# eii-psu-thr-hole-psb.net
KiCad netlist of a schematic drawn in EAGLE
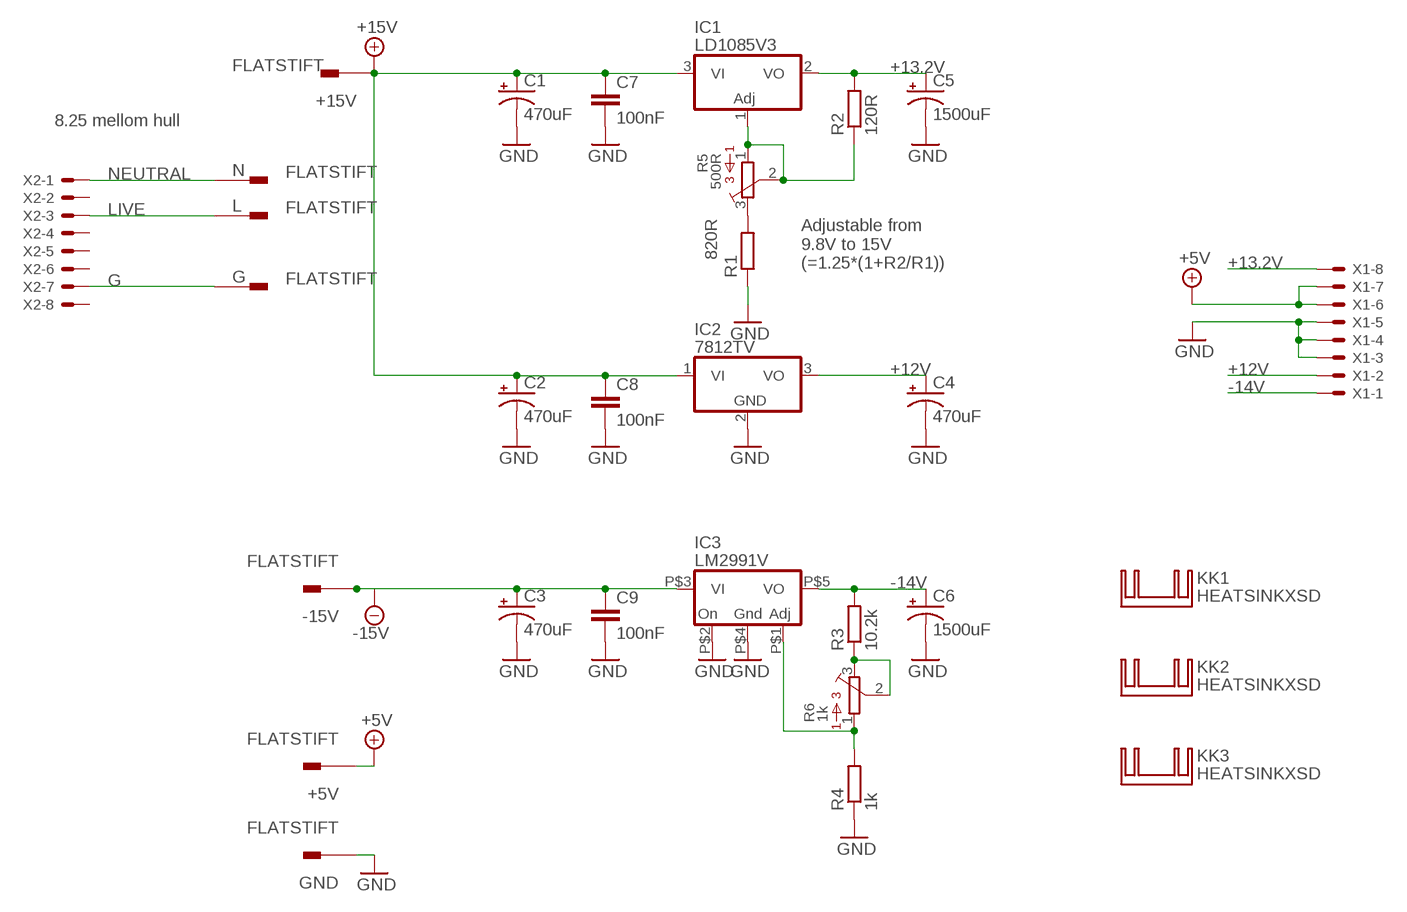
[diagram p0: schematic, sheet 1]

(export (version "E")
  (design (tool "Eeschema 10.0.6"))
  (components
    (comp (ref "+5V")
      (value "FLATSTIFT")
      (footprint "eagle-import:FLATSTIFT")
      (libsource (lib "eagle-import") (part "FLATSTIFT"))
    )
    (comp (ref "+15V")
      (value "FLATSTIFT")
      (footprint "eagle-import:FLATSTIFT")
      (libsource (lib "eagle-import") (part "FLATSTIFT"))
    )
    (comp (ref "-15V")
      (value "FLATSTIFT")
      (footprint "eagle-import:FLATSTIFT")
      (libsource (lib "eagle-import") (part "FLATSTIFT"))
    )
    (comp (ref "C1")
      (value "470uF")
      (footprint "eagle-import:E5-10,5")
      (libsource (lib "eagle-import") (part "CPOL-USE5-10.5"))
    )
    (comp (ref "C2")
      (value "470uF")
      (footprint "eagle-import:E5-10,5")
      (libsource (lib "eagle-import") (part "CPOL-USE5-10.5"))
    )
    (comp (ref "C3")
      (value "470uF")
      (footprint "eagle-import:E5-10,5")
      (libsource (lib "eagle-import") (part "CPOL-USE5-10.5"))
    )
    (comp (ref "C4")
      (value "470uF")
      (footprint "eagle-import:E5-10,5")
      (libsource (lib "eagle-import") (part "CPOL-USE5-10.5"))
    )
    (comp (ref "C5")
      (value "1500uF")
      (footprint "eagle-import:E5-13")
      (libsource (lib "eagle-import") (part "CPOL-USE5-13"))
    )
    (comp (ref "C6")
      (value "1500uF")
      (footprint "eagle-import:E5-13")
      (libsource (lib "eagle-import") (part "CPOL-USE5-13"))
    )
    (comp (ref "C7")
      (value "100nF")
      (footprint "eagle-import:C050-030X075")
      (libsource (lib "eagle-import") (part "C-EU050-030X075"))
    )
    (comp (ref "C8")
      (value "100nF")
      (footprint "eagle-import:C050-030X075")
      (libsource (lib "eagle-import") (part "C-EU050-030X075"))
    )
    (comp (ref "C9")
      (value "100nF")
      (footprint "eagle-import:C050-030X075")
      (libsource (lib "eagle-import") (part "C-EU050-030X075"))
    )
    (comp (ref "G")
      (value "FLATSTIFT")
      (footprint "eagle-import:FLATSTIFT")
      (libsource (lib "eagle-import") (part "FLATSTIFT"))
    )
    (comp (ref "GND")
      (value "FLATSTIFT")
      (footprint "eagle-import:FLATSTIFT")
      (libsource (lib "eagle-import") (part "FLATSTIFT"))
    )
    (comp (ref "IC1")
      (value "LD1085V3")
      (footprint "eagle-import:TO220V-J")
      (libsource (lib "eagle-import") (part "LD1085V3"))
    )
    (comp (ref "IC2")
      (value "7812TV")
      (footprint "eagle-import:TO220V")
      (libsource (lib "eagle-import") (part "78TV12"))
    )
    (comp (ref "IC3")
      (value "LM2991V")
      (footprint "eagle-import:TO220-5V-J")
      (libsource (lib "eagle-import") (part "LM2991V"))
    )
    (comp (ref "KK1")
      (value "HEATSINKXSD")
      (footprint "eagle-import:XSD1226-005")
      (libsource (lib "eagle-import") (part "HEATSINKXSD"))
    )
    (comp (ref "KK2")
      (value "HEATSINKXSD")
      (footprint "eagle-import:XSD1226-005")
      (libsource (lib "eagle-import") (part "HEATSINKXSD"))
    )
    (comp (ref "KK3")
      (value "HEATSINKXSD")
      (footprint "eagle-import:XSD1226-005")
      (libsource (lib "eagle-import") (part "HEATSINKXSD"))
    )
    (comp (ref "L")
      (value "FLATSTIFT")
      (footprint "eagle-import:FLATSTIFT")
      (libsource (lib "eagle-import") (part "FLATSTIFT"))
    )
    (comp (ref "N")
      (value "FLATSTIFT")
      (footprint "eagle-import:FLATSTIFT")
      (libsource (lib "eagle-import") (part "FLATSTIFT"))
    )
    (comp (ref "R1")
      (value "820R")
      (footprint "eagle-import:0207_7")
      (libsource (lib "eagle-import") (part "R-EU_0207/7"))
    )
    (comp (ref "R2")
      (value "120R")
      (footprint "eagle-import:0207_7")
      (libsource (lib "eagle-import") (part "R-EU_0207/7"))
    )
    (comp (ref "R3")
      (value "10.2k")
      (footprint "eagle-import:0207_7")
      (libsource (lib "eagle-import") (part "R-EU_0207/7"))
    )
    (comp (ref "R4")
      (value "1k")
      (footprint "eagle-import:0207_7")
      (libsource (lib "eagle-import") (part "R-EU_0207/7"))
    )
    (comp (ref "R5")
      (value "500R")
      (footprint "eagle-import:3362P")
      (libsource (lib "eagle-import") (part "3362P"))
    )
    (comp (ref "R6")
      (value "1k")
      (footprint "eagle-import:3362P")
      (libsource (lib "eagle-import") (part "3362P"))
    )
    (comp (ref "X1")
      (value "KK-156-8")
      (footprint "eagle-import:KK-156-8")
      (fields (field (name "MF") "MOLEX"))
      (libsource (lib "eagle-import") (part "KK-156-8"))
    )
    (comp (ref "X2")
      (value "KK-156-8")
      (footprint "eagle-import:KK-156-8")
      (fields (field (name "MF") "MOLEX"))
      (libsource (lib "eagle-import") (part "KK-156-8"))
    )
  )
  (nets
    (net (code "1") (name "+5V") (class "Default")
      (node (ref "+5V") (pin "F") (pinfunction "1_F") (pintype "passive"))
      (node (ref "+5V") (pin "F2") (pinfunction "1_F2") (pintype "passive"))
      (node (ref "X1") (pin "6") (pinfunction "S_6") (pintype "passive"))
      (node (ref "X1") (pin "7") (pinfunction "S_7") (pintype "passive"))
    )
    (net (code "2") (name "+15V") (class "Default")
      (node (ref "+15V") (pin "F") (pinfunction "1_F") (pintype "passive"))
      (node (ref "+15V") (pin "F2") (pinfunction "1_F2") (pintype "passive"))
      (node (ref "C1") (pin "+") (pinfunction "+_+") (pintype "passive"))
      (node (ref "C2") (pin "+") (pinfunction "+_+") (pintype "passive"))
      (node (ref "C7") (pin "1") (pinfunction "1_1") (pintype "passive"))
      (node (ref "C8") (pin "1") (pinfunction "1_1") (pintype "passive"))
      (node (ref "IC1") (pin "3") (pinfunction "VI_3") (pintype "input"))
      (node (ref "IC2") (pin "1") (pinfunction "VI_1") (pintype "input"))
    )
    (net (code "3") (name "-15V") (class "Default")
      (node (ref "-15V") (pin "F") (pinfunction "1_F") (pintype "passive"))
      (node (ref "-15V") (pin "F2") (pinfunction "1_F2") (pintype "passive"))
      (node (ref "C3") (pin "+") (pinfunction "+_+") (pintype "passive"))
      (node (ref "C9") (pin "1") (pinfunction "1_1") (pintype "passive"))
      (node (ref "IC3") (pin "P$3") (pinfunction "VI_P$3") (pintype "input"))
    )
    (net (code "4") (name "/+12V") (class "Default")
      (node (ref "C4") (pin "+") (pinfunction "+_+") (pintype "passive"))
      (node (ref "IC2") (pin "3") (pinfunction "VO_3") (pintype "passive"))
      (node (ref "X1") (pin "2") (pinfunction "S_2") (pintype "passive"))
    )
    (net (code "5") (name "/+13.2V") (class "Default")
      (node (ref "C5") (pin "+") (pinfunction "+_+") (pintype "passive"))
      (node (ref "IC1") (pin "2") (pinfunction "VO_2") (pintype "passive"))
      (node (ref "R2") (pin "2") (pinfunction "2_2") (pintype "passive"))
      (node (ref "X1") (pin "8") (pinfunction "S_8") (pintype "passive"))
    )
    (net (code "6") (name "/-14V") (class "Default")
      (node (ref "C6") (pin "+") (pinfunction "+_+") (pintype "passive"))
      (node (ref "IC3") (pin "P$5") (pinfunction "VO_P$5") (pintype "passive"))
      (node (ref "R3") (pin "2") (pinfunction "2_2") (pintype "passive"))
      (node (ref "X1") (pin "1") (pinfunction "S_1") (pintype "passive"))
    )
    (net (code "7") (name "/G") (class "Default")
      (node (ref "G") (pin "F") (pinfunction "1_F") (pintype "passive"))
      (node (ref "G") (pin "F2") (pinfunction "1_F2") (pintype "passive"))
      (node (ref "X2") (pin "7") (pinfunction "S_7") (pintype "passive"))
    )
    (net (code "8") (name "/LIVE") (class "Default")
      (node (ref "L") (pin "F") (pinfunction "1_F") (pintype "passive"))
      (node (ref "L") (pin "F2") (pinfunction "1_F2") (pintype "passive"))
      (node (ref "X2") (pin "3") (pinfunction "S_3") (pintype "passive"))
    )
    (net (code "9") (name "/NEUTRAL") (class "Default")
      (node (ref "N") (pin "F") (pinfunction "1_F") (pintype "passive"))
      (node (ref "N") (pin "F2") (pinfunction "1_F2") (pintype "passive"))
      (node (ref "X2") (pin "1") (pinfunction "S_1") (pintype "passive"))
    )
    (net (code "10") (name "GND") (class "Default")
      (node (ref "C1") (pin "-") (pinfunction "-_-") (pintype "passive"))
      (node (ref "C2") (pin "-") (pinfunction "-_-") (pintype "passive"))
      (node (ref "C3") (pin "-") (pinfunction "-_-") (pintype "passive"))
      (node (ref "C4") (pin "-") (pinfunction "-_-") (pintype "passive"))
      (node (ref "C5") (pin "-") (pinfunction "-_-") (pintype "passive"))
      (node (ref "C6") (pin "-") (pinfunction "-_-") (pintype "passive"))
      (node (ref "C7") (pin "2") (pinfunction "2_2") (pintype "passive"))
      (node (ref "C8") (pin "2") (pinfunction "2_2") (pintype "passive"))
      (node (ref "C9") (pin "2") (pinfunction "2_2") (pintype "passive"))
      (node (ref "GND") (pin "F") (pinfunction "1_F") (pintype "passive"))
      (node (ref "GND") (pin "F2") (pinfunction "1_F2") (pintype "passive"))
      (node (ref "IC2") (pin "2") (pinfunction "GND_2") (pintype "passive"))
      (node (ref "IC3") (pin "P$2") (pinfunction "ON_P$2") (pintype "passive"))
      (node (ref "IC3") (pin "P$4") (pinfunction "GND_P$4") (pintype "passive"))
      (node (ref "R1") (pin "1") (pinfunction "1_1") (pintype "passive"))
      (node (ref "R4") (pin "1") (pinfunction "1_1") (pintype "passive"))
      (node (ref "X1") (pin "3") (pinfunction "S_3") (pintype "passive"))
      (node (ref "X1") (pin "4") (pinfunction "S_4") (pintype "passive"))
      (node (ref "X1") (pin "5") (pinfunction "S_5") (pintype "passive"))
    )
    (net (code "11") (name "Net-(IC1-ADJ)") (class "Default")
      (node (ref "IC1") (pin "1") (pinfunction "ADJ_1") (pintype "passive"))
      (node (ref "R2") (pin "1") (pinfunction "1_1") (pintype "passive"))
      (node (ref "R5") (pin "1") (pinfunction "1_1") (pintype "passive"))
      (node (ref "R5") (pin "2") (pinfunction "2_2") (pintype "passive"))
    )
    (net (code "12") (name "Net-(IC3-ADJ)") (class "Default")
      (node (ref "IC3") (pin "P$1") (pinfunction "ADJ_P$1") (pintype "passive"))
      (node (ref "R4") (pin "2") (pinfunction "2_2") (pintype "passive"))
      (node (ref "R6") (pin "1") (pinfunction "1_1") (pintype "passive"))
    )
    (net (code "13") (name "Net-(R1-Pad2)") (class "Default")
      (node (ref "R1") (pin "2") (pinfunction "2_2") (pintype "passive"))
      (node (ref "R5") (pin "3") (pinfunction "3_3") (pintype "passive"))
    )
    (net (code "14") (name "Net-(R3-Pad1)") (class "Default")
      (node (ref "R3") (pin "1") (pinfunction "1_1") (pintype "passive"))
      (node (ref "R6") (pin "2") (pinfunction "2_2") (pintype "passive"))
      (node (ref "R6") (pin "3") (pinfunction "3_3") (pintype "passive"))
    )
    (net (code "15") (name "unconnected-(X2B-S-Pad2)") (class "Default")
      (node (ref "X2") (pin "2") (pinfunction "S_2") (pintype "passive"))
    )
    (net (code "16") (name "unconnected-(X2D-S-Pad4)") (class "Default")
      (node (ref "X2") (pin "4") (pinfunction "S_4") (pintype "passive"))
    )
    (net (code "17") (name "unconnected-(X2E-S-Pad5)") (class "Default")
      (node (ref "X2") (pin "5") (pinfunction "S_5") (pintype "passive"))
    )
    (net (code "18") (name "unconnected-(X2F-S-Pad6)") (class "Default")
      (node (ref "X2") (pin "6") (pinfunction "S_6") (pintype "passive"))
    )
    (net (code "19") (name "unconnected-(X2H-S-Pad8)") (class "Default")
      (node (ref "X2") (pin "8") (pinfunction "S_8") (pintype "passive"))
    )
  )
)
